# Main.net
KiCad netlist of a schematic drawn in Altium Designer
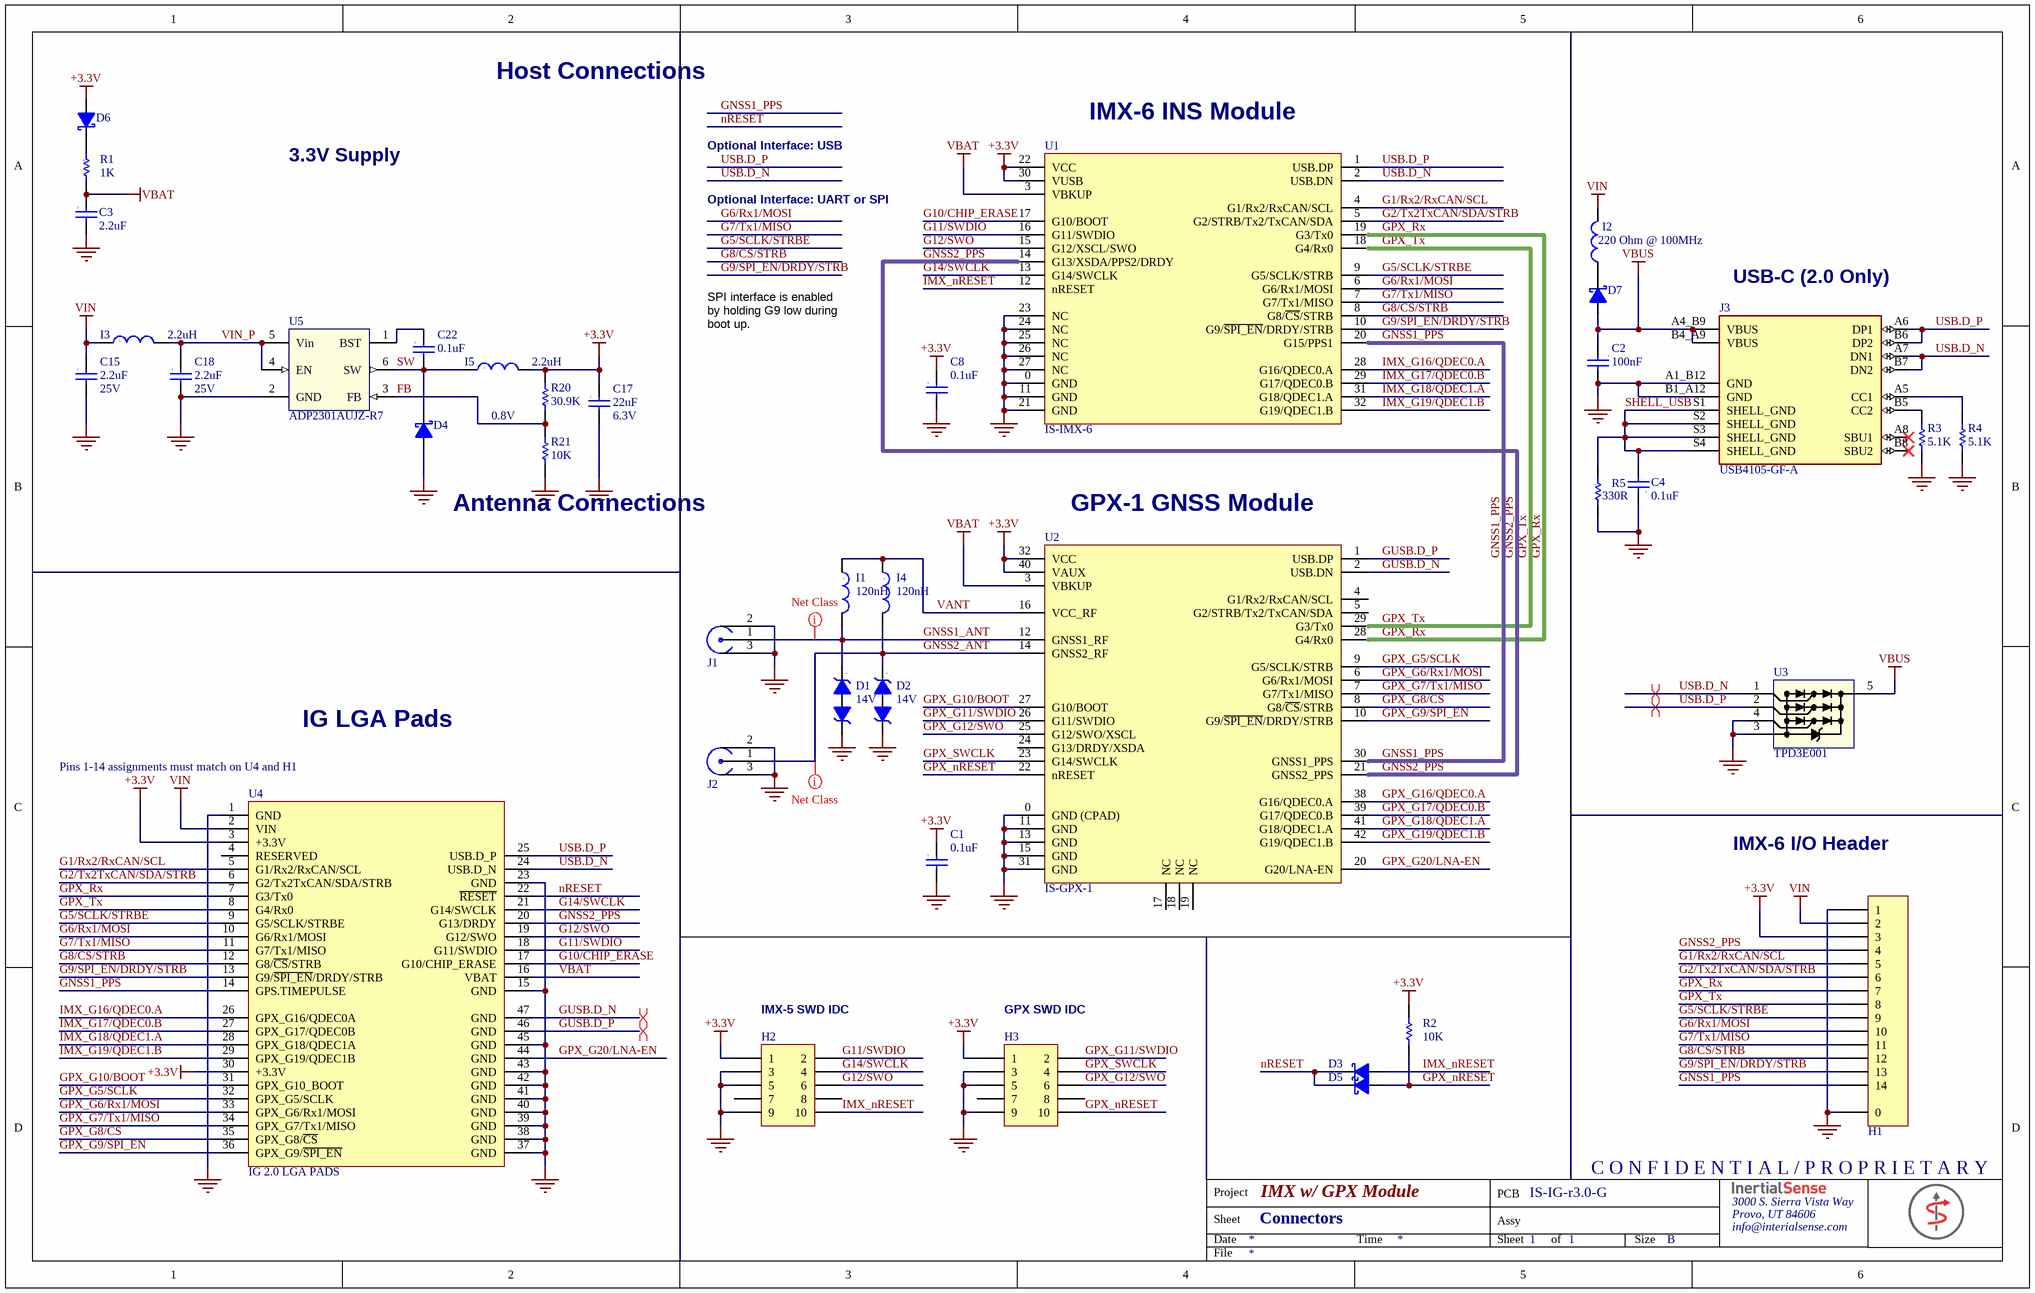
[diagram p0: Main.SchDoc]

(export (version "E")
  (design (tool "Eeschema 10.0.6"))
  (components
    (comp (ref "C1")
      (value "0.1uF")
      (footprint "0402")
      (description "CAP CER .10UF 50V X7R 10% 0402")
      (fields
        (field (name "MANUFACTURER") "TDK Corporation")
        (field (name "MANUFACTURER PART NUMBER") "C1005X7R1H104K")
        (field (name "PUBLISHER") "Altium Limited")
      )
      (libsource (lib "General") (part "Cap"))
    )
    (comp (ref "C2")
      (value "100nF")
      (footprint "0402")
      (description "CAP CER .10UF 50V X7R 10% 0402")
      (fields
        (field (name "MANUFACTURER") "TDK Corporation")
        (field (name "MANUFACTURER PART NUMBER") "C1005X7R1H104K")
        (field (name "PUBLISHER") "Altium Limited")
      )
      (libsource (lib "General") (part "Cap"))
    )
    (comp (ref "C3")
      (value "2.2uF")
      (footprint "0402")
      (description "0402 2.2 uF 6.3 V ±10% Tolerance X6S Multilayer Ceramic Capacitor")
      (fields
        (field (name "MANUFACTURER") "Murata")
        (field (name "MANUFACTURER PART NUMBER") "GRM155C80J225KE95D")
        (field (name "PUBLISHER") "Altium Limited")
      )
      (libsource (lib "General") (part "Cap"))
    )
    (comp (ref "C4")
      (value "0.1uF")
      (footprint "0402")
      (description "CAP CER .10UF 50V X7R 10% 0402")
      (fields
        (field (name "MANUFACTURER") "TDK Corporation")
        (field (name "MANUFACTURER PART NUMBER") "C1005X7R1H104K")
        (field (name "PUBLISHER") "Altium Limited")
      )
      (libsource (lib "General") (part "Cap"))
    )
    (comp (ref "C8")
      (value "0.1uF")
      (footprint "0402")
      (description "CAP CER .10UF 50V X7R 10% 0402")
      (fields
        (field (name "MANUFACTURER") "TDK Corporation")
        (field (name "MANUFACTURER PART NUMBER") "C1005X7R1H104K")
        (field (name "PUBLISHER") "Altium Limited")
      )
      (libsource (lib "General") (part "Cap"))
    )
    (comp (ref "C15")
      (value "2.2uF")
      (footprint "0603")
      (description "CAP CER 2.2UF 25V X6S 0603")
      (fields
        (field (name "MANUFACTURER") "Murata")
        (field (name "MANUFACTURER PART NUMBER") "GRT188C81E225KE13D")
        (field (name "VOLTAGE RATING") "25V")
        (field (name "PUBLISHER") "Altium Limited")
      )
      (libsource (lib "General") (part "Cap"))
    )
    (comp (ref "C17")
      (value "22uF")
      (footprint "0603")
      (description "CAP CER 22UF 6.3V X6S 0603")
      (fields
        (field (name "MANUFACTURER") "Murata")
        (field (name "MANUFACTURER PART NUMBER") "GRM188C80J226ME15D")
        (field (name "VOLTAGE RATING") "6.3V")
        (field (name "PUBLISHER") "Altium Limited")
      )
      (libsource (lib "General") (part "Cap"))
    )
    (comp (ref "C18")
      (value "2.2uF")
      (footprint "0603")
      (description "CAP CER 2.2UF 25V X6S 0603")
      (fields
        (field (name "MANUFACTURER") "Murata")
        (field (name "MANUFACTURER PART NUMBER") "GRT188C81E225KE13D")
        (field (name "VOLTAGE RATING") "25V")
        (field (name "PUBLISHER") "Altium Limited")
      )
      (libsource (lib "General") (part "Cap"))
    )
    (comp (ref "C22")
      (value "0.1uF")
      (footprint "0402")
      (description "CAP CER 0.1UF 50V X7R 0402")
      (fields
        (field (name "MANUFACTURER") "TDK")
        (field (name "MANUFACTURER PART NUMBER") "CGA2B3X7R1H104K050BB")
        (field (name "PUBLISHER") "Altium Limited")
      )
      (libsource (lib "General") (part "Cap"))
    )
    (comp (ref "D1")
      (value "Diode - Bidirectional Zener")
      (footprint "R0402")
      (description "LITTELFUSE - PESD0402-140 - DIODE, ESD PROTECTION, 0402, FULL REEL")
      (fields
        (field (name "MANUFACTURER") "Littelfuse")
        (field (name "MANUFACTURER PART NUMBER") "PESD0402-140")
        (field (name "WORKING VOLTAGE") "14V")
      )
      (libsource (lib "General") (part "Diode - Bidirectional Zener"))
    )
    (comp (ref "D2")
      (value "Diode - Bidirectional Zener")
      (footprint "R0402")
      (description "LITTELFUSE - PESD0402-140 - DIODE, ESD PROTECTION, 0402, FULL REEL")
      (fields
        (field (name "MANUFACTURER") "Littelfuse")
        (field (name "MANUFACTURER PART NUMBER") "PESD0402-140")
        (field (name "WORKING VOLTAGE") "14V")
      )
      (libsource (lib "General") (part "Diode - Bidirectional Zener"))
    )
    (comp (ref "D3")
      (value "Diode - Schottky")
      (footprint "D0402")
      (description "CDBQR0130L; SMT Schottky Diode; 35V 100mA; 2-Pin SOD-923F (0402)")
      (fields (field (name "MANUFACTURER") "Comchip") (field (name "MANUFACTURER PART NUMBER") "CDBQR0130L"))
      (libsource (lib "General") (part "Diode - Schottky"))
    )
    (comp (ref "D4")
      (value "Diode - Schottky")
      (footprint "D0603B")
      (description "DIODE SCHOTTKY 30V 2A 0603")
      (fields
        (field (name "MANUFACTURER") "Vishay")
        (field (name "MANUFACTURER PART NUMBER") "VSKY20301608-G4-08")
      )
      (libsource (lib "General") (part "Diode - Schottky"))
    )
    (comp (ref "D5")
      (value "Diode - Schottky")
      (footprint "D0402")
      (description "CDBQR0130L; SMT Schottky Diode; 35V 100mA; 2-Pin SOD-923F (0402)")
      (fields (field (name "MANUFACTURER") "Comchip") (field (name "MANUFACTURER PART NUMBER") "CDBQR0130L"))
      (libsource (lib "General") (part "Diode - Schottky"))
    )
    (comp (ref "D6")
      (value "Diode - Schottky")
      (footprint "D0603B")
      (description "DIODE SCHOTTKY 30V 2A 0603")
      (fields
        (field (name "MANUFACTURER") "Vishay")
        (field (name "MANUFACTURER PART NUMBER") "VSKY20301608-G4-08")
      )
      (libsource (lib "General") (part "Diode - Schottky"))
    )
    (comp (ref "D7")
      (value "Diode - Schottky")
      (footprint "D0603B")
      (description "DIODE SCHOTTKY 30V 2A 0603")
      (fields
        (field (name "MANUFACTURER") "Vishay")
        (field (name "MANUFACTURER PART NUMBER") "VSKY20301608-G4-08")
      )
      (libsource (lib "General") (part "Diode - Schottky"))
    )
    (comp (ref "H1")
      (value "Hdr - 14pin - mount")
      (footprint "SM14B-GHS-TB(LF)(SN)")
      (description "Conn Shrouded Header HDR 14 POS 1.25mm Solder ST Top Entry SMD T/R")
      (fields
        (field (name "MANUFACTURER") "JST")
        (field (name "MANUFACTURER PART NUMBER") "SM14B-GHS-TB(LF)(SN)")
      )
      (libsource (lib "Connectors") (part "Hdr - 14pin - mount"))
    )
    (comp (ref "H2")
      (value "Hdr - 5x2pin")
      (footprint "FTSH-105-01-L-DV-K-A-P")
      (description "CONN HEADER 10POS DUAL .05\" SMD")
      (fields
        (field (name "MANUFACTURER") "Samtec")
        (field (name "MANUFACTURER PART NUMBER") "FTSH-105-01-L-DV-K-A-P")
      )
      (libsource (lib "Connectors") (part "Hdr - 5x2pin"))
    )
    (comp (ref "H3")
      (value "Hdr - 5x2pin")
      (footprint "FTSH-105-01-L-DV-K-A-P")
      (description "CONN HEADER 10POS DUAL .05\" SMD")
      (fields
        (field (name "MANUFACTURER") "Samtec")
        (field (name "MANUFACTURER PART NUMBER") "FTSH-105-01-L-DV-K-A-P")
      )
      (libsource (lib "Connectors") (part "Hdr - 5x2pin"))
    )
    (comp (ref "I1")
      (value "120nH")
      (footprint "0402")
      (description "Inductor RF Chip Wirewound 120nH 5% 100MHz 20Q-Factor 110mA 2.66Ohm DCR 0402 Paper T/R")
      (fields
        (field (name "MANUFACTURER") "Murata")
        (field (name "MANUFACTURER PART NUMBER") "LQW15ANR12J00D")
      )
      (libsource (lib "") (part "Inductor_1"))
    )
    (comp (ref "I2")
      (value "220 Ohm @ 100MHz")
      (footprint "I0603")
      (description "FERRITE CHIP 220 OHM 2500MA 0603")
      (fields
        (field (name "MANUFACTURER") "Murata Electronics North America")
        (field (name "MANUFACTURER PART NUMBER") "BLM18SG221TN1D")
      )
      (libsource (lib "General") (part "Inductor"))
    )
    (comp (ref "I3")
      (value "2.2uH")
      (footprint "0806")
      (description "FIXED IND 2.2UH 1.2A 110 MOHM")
      (fields
        (field (name "MANUFACTURER") "TDK")
        (field (name "MANUFACTURER PART NUMBER") "MLP2016H2R2MT0S1")
      )
      (libsource (lib "") (part "Inductor_1"))
    )
    (comp (ref "I4")
      (value "120nH")
      (footprint "0402")
      (description "Inductor RF Chip Wirewound 120nH 5% 100MHz 20Q-Factor 110mA 2.66Ohm DCR 0402 Paper T/R")
      (fields
        (field (name "MANUFACTURER") "Murata")
        (field (name "MANUFACTURER PART NUMBER") "LQW15ANR12J00D")
      )
      (libsource (lib "") (part "Inductor_1"))
    )
    (comp (ref "I5")
      (value "2.2uH")
      (footprint "0806")
      (description "FIXED IND 2.2UH 1.2A 110 MOHM")
      (fields
        (field (name "MANUFACTURER") "TDK")
        (field (name "MANUFACTURER PART NUMBER") "MLP2016H2R2MT0S1")
      )
      (libsource (lib "") (part "Inductor_1"))
    )
    (comp (ref "J1")
      (value "RF - GND x 2")
      (footprint "RF UMC SMD")
      (description "CONN UMC RCPT STR 50 OHM SMD")
      (fields
        (field (name "MANUFACTURER") "Emerson Network Power Connectivity Johnson")
        (field (name "MANUFACTURER PART NUMBER") "128-0711-201")
      )
      (libsource (lib "Connectors") (part "RF - GND x 2"))
    )
    (comp (ref "J2")
      (value "RF - GND x 2")
      (footprint "RF UMC SMD")
      (description "CONN UMC RCPT STR 50 OHM SMD")
      (fields
        (field (name "MANUFACTURER") "Emerson Network Power Connectivity Johnson")
        (field (name "MANUFACTURER PART NUMBER") "128-0711-201")
      )
      (libsource (lib "Connectors") (part "RF - GND x 2"))
    )
    (comp (ref "J3")
      (value "USB4105-GF-A")
      (footprint "GCT_USB4105-GF-A")
      (fields (field (name "MANUFACTURER") "GCT"))
      (libsource (lib "Connectors") (part "USB4105-GF-A"))
    )
    (comp (ref "R1")
      (value "1K")
      (footprint "R0402")
      (description "1 kOhms ±1% 0.063W, 1/16W Chip Resistor 0402 (1005 Metric) Moisture Resistant Thick Film")
      (fields
        (field (name "MANUFACTURER") "Yageo")
        (field (name "MANUFACTURER PART NUMBER") "RC0402FR-071KL")
      )
      (libsource (lib "General") (part "Res"))
    )
    (comp (ref "R2")
      (value "10K")
      (footprint "R0402")
      (description "10 kOhms 1% 0.063W, 1/16W Chip Resistor 0402 (1005 Metric) Moisture Resistant Thick Film")
      (fields
        (field (name "MANUFACTURER") "Stackpole Electronics")
        (field (name "MANUFACTURER PART NUMBER") "RMCF0402FT10K0")
      )
      (libsource (lib "General") (part "Res"))
    )
    (comp (ref "R3")
      (value "5.1K")
      (footprint "R0402")
      (description "Res Thick Film 1.0 x 0.5 mm 5.1K Ohm 1% 0.063W(1/16W) 100ppm/ C Molded SMD Paper T/R")
      (fields
        (field (name "MANUFACTURER") "Yageo")
        (field (name "MANUFACTURER PART NUMBER") "RC0402FR-075K1L")
      )
      (libsource (lib "General") (part "Res"))
    )
    (comp (ref "R4")
      (value "5.1K")
      (footprint "R0402")
      (description "Res Thick Film 1.0 x 0.5 mm 5.1K Ohm 1% 0.063W(1/16W) 100ppm/ C Molded SMD Paper T/R")
      (fields
        (field (name "MANUFACTURER") "Yageo")
        (field (name "MANUFACTURER PART NUMBER") "RC0402FR-075K1L")
      )
      (libsource (lib "General") (part "Res"))
    )
    (comp (ref "R5")
      (value "330R")
      (footprint "R0402")
      (description "Res Thick Film 0402 0.33 Ohm 1% 0.125W(1/8W) ±100ppm/C Sulfur Resistant Pad SMD Automotive T/R")
      (fields
        (field (name "MANUFACTURER") "Vishay Dale")
        (field (name "MANUFACTURER PART NUMBER") "RCWE0402R330FKEA")
      )
      (libsource (lib "General") (part "Res"))
    )
    (comp (ref "R20")
      (value "30.9K")
      (footprint "R0402")
      (description "RES TF 30.9K OHM 1% 1/16W 0402")
      (fields
        (field (name "MANUFACTURER") "Stackpole Electronics Inc")
        (field (name "MANUFACTURER PART NUMBER") "RMCF0402FT30K9")
      )
      (libsource (lib "General") (part "Res"))
    )
    (comp (ref "R21")
      (value "10K")
      (footprint "R0402")
      (description "RES 10.0K OHM 1/16W 1% 0402 SMD")
      (fields
        (field (name "MANUFACTURER") "Yageo")
        (field (name "MANUFACTURER PART NUMBER") "RC0402FR-0710KL")
      )
      (libsource (lib "General") (part "Res"))
    )
    (comp (ref "U1")
      (value "IMX")
      (footprint "IS-IMX-6")
      (description "Inertial Sense IMX")
      (fields
        (field (name "MANUFACTURER") "Inertial Sense")
        (field (name "MANUFACTURER PART NUMBER") "IS-IMX-6")
      )
      (libsource (lib "IS-IMX-6") (part "IS-IMX-6"))
    )
    (comp (ref "U2")
      (value "GPX")
      (footprint "IS-GPX-1.0")
      (description "Inertial Sense GPX")
      (fields
        (field (name "MANUFACTURER") "Inertial Sense")
        (field (name "MANUFACTURER PART NUMBER") "IS-GPX-1")
      )
      (libsource (lib "IS-GPX-1") (part "IS-GPX-1.0"))
    )
    (comp (ref "U3")
      (value "TPD3E001")
      (footprint "SOTFL50P160X60-5N")
      (description "TVS DIODE 5.5V SOT5")
      (fields
        (field (name "MANUFACTURER") "Texas Instruments")
        (field (name "MANUFACTURER PART NUMBER") "TPD3E001DRLR")
      )
      (libsource (lib "ICs") (part "TPD3E001"))
    )
    (comp (ref "U4")
      (value "IG 2.0 LGA PADS")
      (footprint "IG-2.0_LGA")
      (description "IMX multi-frequency RTK-GNSS Module")
      (libsource (lib "Sensors") (part "IG_2.0_LGA"))
    )
    (comp (ref "U5")
      (value "ADP2301")
      (footprint "MO-178-AB")
      (description "IC BUCK ADJ 1.2A 6TSOT")
      (fields
        (field (name "MANUFACTURER") "Analog Devices Inc")
        (field (name "MANUFACTURER PART NUMBER") "ADP2301AUJZ-R7")
      )
      (libsource (lib "ICs") (part "ADP2301"))
    )
  )
  (nets
    (net (code "1") (name "+3.3V") (class "Default")
      (node (ref "C1") (pin "1") (pinfunction "1_1") (pintype "passive"))
      (node (ref "C17") (pin "1") (pinfunction "1_1") (pintype "passive"))
      (node (ref "C8") (pin "1") (pinfunction "1_1") (pintype "passive"))
      (node (ref "D6") (pin "A") (pinfunction "A_A") (pintype "passive"))
      (node (ref "H1") (pin "3") (pinfunction "3_3") (pintype "passive"))
      (node (ref "H2") (pin "1") (pinfunction "1_1") (pintype "passive"))
      (node (ref "H3") (pin "1") (pinfunction "1_1") (pintype "passive"))
      (node (ref "I5") (pin "2") (pinfunction "2_2") (pintype "passive"))
      (node (ref "R2") (pin "1") (pinfunction "1_1") (pintype "passive"))
      (node (ref "R20") (pin "2") (pinfunction "2_2") (pintype "passive"))
      (node (ref "U1") (pin "22") (pinfunction "VCC_22") (pintype "power_in"))
      (node (ref "U1") (pin "30") (pinfunction "VUSB_30") (pintype "power_in"))
      (node (ref "U2") (pin "32") (pinfunction "VCC_32") (pintype "power_in"))
      (node (ref "U2") (pin "40") (pinfunction "VAUX_40") (pintype "power_in"))
      (node (ref "U4") (pin "3") (pinfunction "+3.3V_3") (pintype "passive"))
      (node (ref "U4") (pin "30") (pinfunction "+3.3V_30") (pintype "passive"))
    )
    (net (code "2") (name "/FB") (class "Default")
      (node (ref "R20") (pin "1") (pinfunction "1_1") (pintype "passive"))
      (node (ref "R21") (pin "2") (pinfunction "2_2") (pintype "passive"))
      (node (ref "U5") (pin "3") (pinfunction "FB_3") (pintype "input"))
    )
    (net (code "3") (name "/G1{slash}Rx2{slash}RxCAN{slash}SCL") (class "Default")
      (node (ref "H1") (pin "5") (pinfunction "5_5") (pintype "passive"))
      (node (ref "U1") (pin "4") (pinfunction "G1/Rx2/RxCAN/SCL_4") (pintype "passive"))
      (node (ref "U4") (pin "5") (pinfunction "G1/Rx2/RxCAN/SCL_5") (pintype "passive"))
    )
    (net (code "4") (name "/G2{slash}Tx2TxCAN{slash}SDA{slash}STRB") (class "Default")
      (node (ref "H1") (pin "6") (pinfunction "6_6") (pintype "passive"))
      (node (ref "U1") (pin "5") (pinfunction "G2/STRB/Tx2/TxCAN/SDA_5") (pintype "passive"))
      (node (ref "U4") (pin "6") (pinfunction "G2/Tx2TxCAN/SDA/STRB_6") (pintype "passive"))
    )
    (net (code "5") (name "/G5{slash}SCLK{slash}STRBE") (class "Default")
      (node (ref "H1") (pin "9") (pinfunction "9_9") (pintype "passive"))
      (node (ref "U1") (pin "9") (pinfunction "G5/SCLK/STRB_9") (pintype "passive"))
      (node (ref "U4") (pin "9") (pinfunction "G5/SCLK/STRBE_9") (pintype "passive"))
    )
    (net (code "6") (name "/G6{slash}Rx1{slash}MOSI") (class "Default")
      (node (ref "H1") (pin "10") (pinfunction "10_10") (pintype "passive"))
      (node (ref "U1") (pin "6") (pinfunction "G6/Rx1/MOSI_6") (pintype "passive"))
      (node (ref "U4") (pin "10") (pinfunction "G6/Rx1/MOSI_10") (pintype "passive"))
    )
    (net (code "7") (name "/G7{slash}Tx1{slash}MISO") (class "Default")
      (node (ref "H1") (pin "11") (pinfunction "11_11") (pintype "passive"))
      (node (ref "U1") (pin "7") (pinfunction "G7/Tx1/MISO_7") (pintype "passive"))
      (node (ref "U4") (pin "11") (pinfunction "G7/Tx1/MISO_11") (pintype "passive"))
    )
    (net (code "8") (name "/G8{slash}~{CS}{slash}STRB") (class "Default")
      (node (ref "H1") (pin "12") (pinfunction "12_12") (pintype "passive"))
      (node (ref "U1") (pin "8") (pinfunction "G8/~{CS}/STRB_8") (pintype "passive"))
      (node (ref "U4") (pin "12") (pinfunction "G8/~{CS}/STRB_12") (pintype "passive"))
    )
    (net (code "9") (name "/G9{slash}~{SPI_EN}{slash}DRDY{slash}STRB") (class "Default")
      (node (ref "H1") (pin "13") (pinfunction "13_13") (pintype "passive"))
      (node (ref "U1") (pin "10") (pinfunction "G9/~{SPI_EN}/DRDY/STRB_10") (pintype "passive"))
      (node (ref "U4") (pin "13") (pinfunction "G9/~{SPI_EN}/DRDY/STRB_13") (pintype "passive"))
    )
    (net (code "10") (name "/G10{slash}CHIP_ERASE") (class "Default")
      (node (ref "U1") (pin "17") (pinfunction "G10/BOOT_17") (pintype "passive"))
      (node (ref "U4") (pin "17") (pinfunction "G10/CHIP_ERASE_17") (pintype "passive"))
    )
    (net (code "11") (name "/G11{slash}SWDIO") (class "Default")
      (node (ref "H2") (pin "2") (pinfunction "2_2") (pintype "passive"))
      (node (ref "U1") (pin "16") (pinfunction "G11/SWDIO_16") (pintype "passive"))
      (node (ref "U4") (pin "18") (pinfunction "G11/SWDIO_18") (pintype "passive"))
    )
    (net (code "12") (name "/G12{slash}SWO") (class "Default")
      (node (ref "H2") (pin "6") (pinfunction "6_6") (pintype "passive"))
      (node (ref "U1") (pin "15") (pinfunction "G12/XSCL/SWO_15") (pintype "passive"))
      (node (ref "U4") (pin "19") (pinfunction "G12/SWO_19") (pintype "passive"))
    )
    (net (code "13") (name "/G14{slash}SWCLK") (class "Default")
      (node (ref "H2") (pin "4") (pinfunction "4_4") (pintype "passive"))
      (node (ref "U1") (pin "13") (pinfunction "G14/SWCLK_13") (pintype "passive"))
      (node (ref "U4") (pin "21") (pinfunction "G14/SWCLK_21") (pintype "passive"))
    )
    (net (code "14") (name "/GNSS1_ANT") (class "Default")
      (node (ref "D1") (pin "1") (pinfunction "1_1") (pintype "passive"))
      (node (ref "I1") (pin "2") (pinfunction "2_2") (pintype "passive"))
      (node (ref "J1") (pin "1") (pinfunction "1_1") (pintype "passive"))
      (node (ref "U2") (pin "12") (pinfunction "GNSS1_RF_12") (pintype "passive"))
    )
    (net (code "15") (name "/GNSS1_PPS") (class "Default")
      (node (ref "H1") (pin "14") (pinfunction "14_14") (pintype "passive"))
      (node (ref "U1") (pin "20") (pinfunction "G15/PPS1_20") (pintype "passive"))
      (node (ref "U2") (pin "30") (pinfunction "GNSS1_PPS_30") (pintype "passive"))
      (node (ref "U4") (pin "14") (pinfunction "GPS.TIMEPULSE_14") (pintype "passive"))
    )
    (net (code "16") (name "/GNSS2_ANT") (class "Default")
      (node (ref "D2") (pin "1") (pinfunction "1_1") (pintype "passive"))
      (node (ref "I4") (pin "2") (pinfunction "2_2") (pintype "passive"))
      (node (ref "J2") (pin "1") (pinfunction "1_1") (pintype "passive"))
      (node (ref "U2") (pin "14") (pinfunction "GNSS2_RF_14") (pintype "passive"))
    )
    (net (code "17") (name "/GNSS2_PPS") (class "Default")
      (node (ref "H1") (pin "4") (pinfunction "4_4") (pintype "passive"))
      (node (ref "U1") (pin "14") (pinfunction "G13/XSDA/PPS2/DRDY_14") (pintype "passive"))
      (node (ref "U2") (pin "21") (pinfunction "GNSS2_PPS_21") (pintype "passive"))
      (node (ref "U4") (pin "20") (pinfunction "G13/DRDY_20") (pintype "passive"))
    )
    (net (code "18") (name "/GPX_G5{slash}SCLK") (class "Default")
      (node (ref "U2") (pin "9") (pinfunction "G5/SCLK/STRB_9") (pintype "passive"))
      (node (ref "U4") (pin "32") (pinfunction "GPX_G5/SCLK_32") (pintype "passive"))
    )
    (net (code "19") (name "/GPX_G6{slash}Rx1{slash}MOSI") (class "Default")
      (node (ref "U2") (pin "6") (pinfunction "G6/Rx1/MOSI_6") (pintype "passive"))
      (node (ref "U4") (pin "33") (pinfunction "GPX_G6/Rx1/MOSI_33") (pintype "passive"))
    )
    (net (code "20") (name "/GPX_G7{slash}Tx1{slash}MISO") (class "Default")
      (node (ref "U2") (pin "7") (pinfunction "G7/Tx1/MISO_7") (pintype "passive"))
      (node (ref "U4") (pin "34") (pinfunction "GPX_G7/Tx1/MISO_34") (pintype "passive"))
    )
    (net (code "21") (name "/GPX_G8{slash}~{CS}") (class "Default")
      (node (ref "U2") (pin "8") (pinfunction "G8/~{CS}/STRB_8") (pintype "passive"))
      (node (ref "U4") (pin "35") (pinfunction "GPX_G8/~{CS}_35") (pintype "passive"))
    )
    (net (code "22") (name "/GPX_G9{slash}~{SPI_EN}") (class "Default")
      (node (ref "U2") (pin "10") (pinfunction "G9/~{SPI_EN}/DRDY/STRB_10") (pintype "passive"))
      (node (ref "U4") (pin "36") (pinfunction "GPX_G9/~{SPI_EN}_36") (pintype "passive"))
    )
    (net (code "23") (name "/GPX_G10{slash}BOOT") (class "Default")
      (node (ref "U2") (pin "27") (pinfunction "G10/BOOT_27") (pintype "passive"))
      (node (ref "U4") (pin "31") (pinfunction "GPX_G10_BOOT_31") (pintype "passive"))
    )
    (net (code "24") (name "/GPX_G11{slash}SWDIO") (class "Default")
      (node (ref "H3") (pin "2") (pinfunction "2_2") (pintype "passive"))
      (node (ref "U2") (pin "26") (pinfunction "G11/SWDIO_26") (pintype "passive"))
    )
    (net (code "25") (name "/GPX_G12{slash}SWO") (class "Default")
      (node (ref "H3") (pin "6") (pinfunction "6_6") (pintype "passive"))
      (node (ref "U2") (pin "25") (pinfunction "G12/SWO/XSCL_25") (pintype "passive"))
    )
    (net (code "26") (name "/GPX_G16{slash}QDEC0.A") (class "Default")
      (node (ref "U2") (pin "38") (pinfunction "G16/QDEC0.A_38") (pintype "passive"))
    )
    (net (code "27") (name "/GPX_G17{slash}QDEC0.B") (class "Default")
      (node (ref "U2") (pin "39") (pinfunction "G17/QDEC0.B_39") (pintype "passive"))
    )
    (net (code "28") (name "/GPX_G18{slash}QDEC1.A") (class "Default")
      (node (ref "U2") (pin "41") (pinfunction "G18/QDEC1.A_41") (pintype "passive"))
    )
    (net (code "29") (name "/GPX_G19{slash}QDEC1.B") (class "Default")
      (node (ref "U2") (pin "42") (pinfunction "G19/QDEC1.B_42") (pintype "passive"))
    )
    (net (code "30") (name "/GPX_G20{slash}LNA-EN") (class "Default")
      (node (ref "U2") (pin "20") (pinfunction "G20/LNA-EN_20") (pintype "passive"))
      (node (ref "U4") (pin "44") (pinfunction "GND_44") (pintype "passive"))
    )
    (net (code "31") (name "/GPX_Rx") (class "Default")
      (node (ref "H1") (pin "7") (pinfunction "7_7") (pintype "passive"))
      (node (ref "U1") (pin "19") (pinfunction "G3/Tx0_19") (pintype "passive"))
      (node (ref "U2") (pin "28") (pinfunction "G4/Rx0_28") (pintype "passive"))
      (node (ref "U4") (pin "7") (pinfunction "G3/Tx0_7") (pintype "passive"))
    )
    (net (code "32") (name "/GPX_SWCLK") (class "Default")
      (node (ref "H3") (pin "4") (pinfunction "4_4") (pintype "passive"))
      (node (ref "U2") (pin "23") (pinfunction "G14/SWCLK_23") (pintype "passive"))
    )
    (net (code "33") (name "/GPX_Tx") (class "Default")
      (node (ref "H1") (pin "8") (pinfunction "8_8") (pintype "passive"))
      (node (ref "U1") (pin "18") (pinfunction "G4/Rx0_18") (pintype "passive"))
      (node (ref "U2") (pin "29") (pinfunction "G3/Tx0_29") (pintype "passive"))
      (node (ref "U4") (pin "8") (pinfunction "G4/Rx0_8") (pintype "passive"))
    )
    (net (code "34") (name "/GPX_nRESET") (class "Default")
      (node (ref "D5") (pin "A") (pinfunction "A_A") (pintype "passive"))
      (node (ref "H3") (pin "10") (pinfunction "10_10") (pintype "passive"))
      (node (ref "R2") (pin "2") (pinfunction "2_2") (pintype "passive"))
      (node (ref "U2") (pin "22") (pinfunction "nRESET_22") (pintype "passive"))
    )
    (net (code "35") (name "/GUSB.D_N") (class "Default")
      (node (ref "U2") (pin "2") (pinfunction "USB.DN_2") (pintype "passive"))
      (node (ref "U4") (pin "47") (pinfunction "GND_47") (pintype "passive"))
    )
    (net (code "36") (name "/GUSB.D_P") (class "Default")
      (node (ref "U2") (pin "1") (pinfunction "USB.DP_1") (pintype "passive"))
      (node (ref "U4") (pin "46") (pinfunction "GND_46") (pintype "passive"))
    )
    (net (code "37") (name "/IMX_G16{slash}QDEC0.A") (class "Default")
      (node (ref "U1") (pin "28") (pinfunction "G16/QDEC0.A_28") (pintype "passive"))
      (node (ref "U4") (pin "26") (pinfunction "GPX_G16/QDEC0A_26") (pintype "passive"))
    )
    (net (code "38") (name "/IMX_G17{slash}QDEC0.B") (class "Default")
      (node (ref "U1") (pin "29") (pinfunction "G17/QDEC0.B_29") (pintype "passive"))
      (node (ref "U4") (pin "27") (pinfunction "GPX_G17/QDEC0B_27") (pintype "passive"))
    )
    (net (code "39") (name "/IMX_G18{slash}QDEC1.A") (class "Default")
      (node (ref "U1") (pin "31") (pinfunction "G18/QDEC1.A_31") (pintype "passive"))
      (node (ref "U4") (pin "28") (pinfunction "GPX_G18/QDEC1A_28") (pintype "passive"))
    )
    (net (code "40") (name "/IMX_G19{slash}QDEC1.B") (class "Default")
      (node (ref "U1") (pin "32") (pinfunction "G19/QDEC1.B_32") (pintype "passive"))
      (node (ref "U4") (pin "29") (pinfunction "GPX_G19/QDEC1B_29") (pintype "passive"))
    )
    (net (code "41") (name "/IMX_nRESET") (class "Default")
      (node (ref "D3") (pin "A") (pinfunction "A_A") (pintype "passive"))
      (node (ref "H2") (pin "10") (pinfunction "10_10") (pintype "passive"))
      (node (ref "U1") (pin "12") (pinfunction "nRESET_12") (pintype "passive"))
    )
    (net (code "42") (name "/SHELL_USB") (class "Default")
      (node (ref "C4") (pin "2") (pinfunction "2_2") (pintype "passive"))
      (node (ref "J3") (pin "S1") (pinfunction "SHELL_GND_S1") (pintype "power_in"))
      (node (ref "J3") (pin "S2") (pinfunction "SHELL_GND_S2") (pintype "power_in"))
      (node (ref "J3") (pin "S3") (pinfunction "SHELL_GND_S3") (pintype "power_in"))
      (node (ref "J3") (pin "S4") (pinfunction "SHELL_GND_S4") (pintype "power_in"))
      (node (ref "R5") (pin "1") (pinfunction "1_1") (pintype "passive"))
    )
    (net (code "43") (name "/SW") (class "Default")
      (node (ref "C22") (pin "2") (pinfunction "2_2") (pintype "passive"))
      (node (ref "D4") (pin "C") (pinfunction "C_C") (pintype "passive"))
      (node (ref "I5") (pin "1") (pinfunction "1_1") (pintype "passive"))
      (node (ref "U5") (pin "6") (pinfunction "SW_6") (pintype "output"))
    )
    (net (code "44") (name "/USB.D_N") (class "Default")
      (node (ref "J3") (pin "A7") (pinfunction "DN1_A7") (pintype "bidirectional"))
      (node (ref "J3") (pin "B7") (pinfunction "DN2_B7") (pintype "bidirectional"))
      (node (ref "U1") (pin "2") (pinfunction "USB.DN_2") (pintype "passive"))
      (node (ref "U3") (pin "1") (pintype "passive"))
      (node (ref "U4") (pin "24") (pinfunction "USB.D_N_24") (pintype "passive"))
    )
    (net (code "45") (name "/USB.D_P") (class "Default")
      (node (ref "J3") (pin "A6") (pinfunction "DP1_A6") (pintype "bidirectional"))
      (node (ref "J3") (pin "B6") (pinfunction "DP2_B6") (pintype "bidirectional"))
      (node (ref "U1") (pin "1") (pinfunction "USB.DP_1") (pintype "passive"))
      (node (ref "U3") (pin "2") (pintype "passive"))
      (node (ref "U4") (pin "25") (pinfunction "USB.D_P_25") (pintype "passive"))
    )
    (net (code "46") (name "/VANT") (class "Default")
      (node (ref "I1") (pin "1") (pinfunction "1_1") (pintype "passive"))
      (node (ref "I4") (pin "1") (pinfunction "1_1") (pintype "passive"))
      (node (ref "U2") (pin "16") (pinfunction "VCC_RF_16") (pintype "power_in"))
    )
    (net (code "47") (name "/VIN_P") (class "Default")
      (node (ref "C18") (pin "1") (pinfunction "1_1") (pintype "passive"))
      (node (ref "I3") (pin "2") (pinfunction "2_2") (pintype "passive"))
      (node (ref "U5") (pin "4") (pinfunction "EN_4") (pintype "input"))
      (node (ref "U5") (pin "5") (pinfunction "Vin_5") (pintype "power_in"))
    )
    (net (code "48") (name "/nRESET") (class "Default")
      (node (ref "D3") (pin "C") (pinfunction "C_C") (pintype "passive"))
      (node (ref "D5") (pin "C") (pinfunction "C_C") (pintype "passive"))
      (node (ref "U4") (pin "22") (pinfunction "~{RESET}_22") (pintype "passive"))
    )
    (net (code "49") (name "GND") (class "Default")
      (node (ref "C1") (pin "2") (pinfunction "2_2") (pintype "passive"))
      (node (ref "C15") (pin "2") (pinfunction "2_2") (pintype "passive"))
      (node (ref "C17") (pin "2") (pinfunction "2_2") (pintype "passive"))
      (node (ref "C18") (pin "2") (pinfunction "2_2") (pintype "passive"))
      (node (ref "C2") (pin "2") (pinfunction "2_2") (pintype "passive"))
      (node (ref "C3") (pin "2") (pinfunction "2_2") (pintype "passive"))
      (node (ref "C4") (pin "1") (pinfunction "1_1") (pintype "passive"))
      (node (ref "C8") (pin "2") (pinfunction "2_2") (pintype "passive"))
      (node (ref "D1") (pin "2") (pinfunction "2_2") (pintype "passive"))
      (node (ref "D2") (pin "2") (pinfunction "2_2") (pintype "passive"))
      (node (ref "D4") (pin "A") (pinfunction "A_A") (pintype "passive"))
      (node (ref "H1") (pin "0") (pinfunction "0_0") (pintype "passive"))
      (node (ref "H1") (pin "1") (pinfunction "1_1") (pintype "passive"))
      (node (ref "H2") (pin "3") (pinfunction "3_3") (pintype "passive"))
      (node (ref "H2") (pin "5") (pinfunction "5_5") (pintype "passive"))
      (node (ref "H2") (pin "9") (pinfunction "9_9") (pintype "passive"))
      (node (ref "H3") (pin "3") (pinfunction "3_3") (pintype "passive"))
      (node (ref "H3") (pin "5") (pinfunction "5_5") (pintype "passive"))
      (node (ref "H3") (pin "9") (pinfunction "9_9") (pintype "passive"))
      (node (ref "J1") (pin "2") (pinfunction "2_2") (pintype "passive"))
      (node (ref "J1") (pin "3") (pinfunction "3_3") (pintype "passive"))
      (node (ref "J2") (pin "2") (pinfunction "2_2") (pintype "passive"))
      (node (ref "J2") (pin "3") (pinfunction "3_3") (pintype "passive"))
      (node (ref "J3") (pin "A1_B12") (pinfunction "GND_A1_B12") (pintype "power_in"))
      (node (ref "J3") (pin "B1_A12") (pinfunction "GND_B1_A12") (pintype "power_in"))
      (node (ref "R21") (pin "1") (pinfunction "1_1") (pintype "passive"))
      (node (ref "R3") (pin "1") (pinfunction "1_1") (pintype "passive"))
      (node (ref "R4") (pin "1") (pinfunction "1_1") (pintype "passive"))
      (node (ref "R5") (pin "2") (pinfunction "2_2") (pintype "passive"))
      (node (ref "U1") (pin "0") (pinfunction "GND_0") (pintype "power_in"))
      (node (ref "U1") (pin "11") (pinfunction "GND_11") (pintype "power_in"))
      (node (ref "U1") (pin "21") (pinfunction "GND_21") (pintype "power_in"))
      (node (ref "U1") (pin "23") (pinfunction "NC_23") (pintype "power_in"))
      (node (ref "U1") (pin "24") (pinfunction "NC_24") (pintype "power_in"))
      (node (ref "U1") (pin "25") (pinfunction "NC_25") (pintype "power_in"))
      (node (ref "U1") (pin "26") (pinfunction "NC_26") (pintype "power_in"))
      (node (ref "U1") (pin "27") (pinfunction "NC_27") (pintype "power_in"))
      (node (ref "U2") (pin "0") (pinfunction "GND_(CPAD)_0") (pintype "power_in"))
      (node (ref "U2") (pin "11") (pinfunction "GND_11") (pintype "power_in"))
      (node (ref "U2") (pin "13") (pinfunction "GND_13") (pintype "power_in"))
      (node (ref "U2") (pin "15") (pinfunction "GND_15") (pintype "power_in"))
      (node (ref "U2") (pin "31") (pinfunction "GND_31") (pintype "power_in"))
      (node (ref "U3") (pin "3") (pintype "passive"))
      (node (ref "U3") (pin "4") (pinfunction "nc_4") (pintype "passive"))
      (node (ref "U4") (pin "1") (pinfunction "GND_1") (pintype "passive"))
      (node (ref "U4") (pin "15") (pinfunction "GND_15") (pintype "passive"))
      (node (ref "U4") (pin "23") (pinfunction "GND_23") (pintype "passive"))
      (node (ref "U4") (pin "37") (pinfunction "GND_37") (pintype "passive"))
      (node (ref "U4") (pin "38") (pinfunction "GND_38") (pintype "passive"))
      (node (ref "U4") (pin "39") (pinfunction "GND_39") (pintype "passive"))
      (node (ref "U4") (pin "40") (pinfunction "GND_40") (pintype "passive"))
      (node (ref "U4") (pin "41") (pinfunction "GND_41") (pintype "passive"))
      (node (ref "U4") (pin "42") (pinfunction "GND_42") (pintype "passive"))
      (node (ref "U4") (pin "43") (pinfunction "GND_43") (pintype "passive"))
      (node (ref "U4") (pin "45") (pinfunction "GND_45") (pintype "passive"))
      (node (ref "U5") (pin "2") (pinfunction "GND_2") (pintype "power_in"))
    )
    (net (code "50") (name "Net-(D6-PadC)") (class "Default")
      (node (ref "D6") (pin "C") (pinfunction "C_C") (pintype "passive"))
      (node (ref "R1") (pin "1") (pinfunction "1_1") (pintype "passive"))
    )
    (net (code "51") (name "Net-(D7-PadC)") (class "Default")
      (node (ref "D7") (pin "C") (pinfunction "C_C") (pintype "passive"))
      (node (ref "I2") (pin "2") (pinfunction "2_2") (pintype "passive"))
    )
    (net (code "52") (name "Net-(J3-CC1)") (class "Default")
      (node (ref "J3") (pin "A5") (pinfunction "CC1_A5") (pintype "bidirectional"))
      (node (ref "R4") (pin "2") (pinfunction "2_2") (pintype "passive"))
    )
    (net (code "53") (name "Net-(J3-CC2)") (class "Default")
      (node (ref "J3") (pin "B5") (pinfunction "CC2_B5") (pintype "bidirectional"))
      (node (ref "R3") (pin "2") (pinfunction "2_2") (pintype "passive"))
    )
    (net (code "54") (name "Net-(U5-BST)") (class "Default")
      (node (ref "C22") (pin "1") (pinfunction "1_1") (pintype "passive"))
      (node (ref "U5") (pin "1") (pinfunction "BST_1") (pintype "passive"))
    )
    (net (code "55") (name "VBAT") (class "Default")
      (node (ref "C3") (pin "1") (pinfunction "1_1") (pintype "passive"))
      (node (ref "R1") (pin "2") (pinfunction "2_2") (pintype "passive"))
      (node (ref "U1") (pin "3") (pinfunction "VBKUP_3") (pintype "passive"))
      (node (ref "U2") (pin "3") (pinfunction "VBKUP_3") (pintype "passive"))
      (node (ref "U4") (pin "16") (pinfunction "VBAT_16") (pintype "passive"))
    )
    (net (code "56") (name "VBUS") (class "Default")
      (node (ref "C2") (pin "1") (pinfunction "1_1") (pintype "passive"))
      (node (ref "D7") (pin "A") (pinfunction "A_A") (pintype "passive"))
      (node (ref "J3") (pin "A4_B9") (pinfunction "VBUS_A4_B9") (pintype "passive"))
      (node (ref "J3") (pin "B4_A9") (pinfunction "VBUS_B4_A9") (pintype "passive"))
      (node (ref "U3") (pin "5") (pinfunction "nc_5") (pintype "passive"))
    )
    (net (code "57") (name "VIN") (class "Default")
      (node (ref "C15") (pin "1") (pinfunction "1_1") (pintype "passive"))
      (node (ref "H1") (pin "2") (pinfunction "2_2") (pintype "passive"))
      (node (ref "I2") (pin "1") (pinfunction "1_1") (pintype "passive"))
      (node (ref "I3") (pin "1") (pinfunction "1_1") (pintype "passive"))
      (node (ref "U4") (pin "2") (pinfunction "VIN_2") (pintype "passive"))
    )
    (net (code "58") (name "unconnected-(H2-Pad7)") (class "Default")
      (node (ref "H2") (pin "7") (pinfunction "7_7") (pintype "passive"))
    )
    (net (code "59") (name "unconnected-(H2-Pad8)") (class "Default")
      (node (ref "H2") (pin "8") (pinfunction "8_8") (pintype "passive"))
    )
    (net (code "60") (name "unconnected-(H3-Pad7)") (class "Default")
      (node (ref "H3") (pin "7") (pinfunction "7_7") (pintype "passive"))
    )
    (net (code "61") (name "unconnected-(H3-Pad8)") (class "Default")
      (node (ref "H3") (pin "8") (pinfunction "8_8") (pintype "passive"))
    )
    (net (code "62") (name "unconnected-(J3-SBU1-PadA8)") (class "Default")
      (node (ref "J3") (pin "A8") (pinfunction "SBU1_A8") (pintype "bidirectional+no_connect"))
    )
    (net (code "63") (name "unconnected-(J3-SBU2-PadB8)") (class "Default")
      (node (ref "J3") (pin "B8") (pinfunction "SBU2_B8") (pintype "bidirectional+no_connect"))
    )
    (net (code "64") (name "unconnected-(U2-G1{slash}Rx2{slash}RxCAN{slash}SCL-Pad4)") (class "Default")
      (node (ref "U2") (pin "4") (pinfunction "G1/Rx2/RxCAN/SCL_4") (pintype "passive"))
    )
    (net (code "65") (name "unconnected-(U2-G2{slash}STRB{slash}Tx2{slash}TxCAN{slash}SDA-Pad5)") (class "Default")
      (node (ref "U2") (pin "5") (pinfunction "G2/STRB/Tx2/TxCAN/SDA_5") (pintype "passive"))
    )
    (net (code "66") (name "unconnected-(U2-G13{slash}DRDY{slash}XSDA-Pad24)") (class "Default")
      (node (ref "U2") (pin "24") (pinfunction "G13/DRDY/XSDA_24") (pintype "passive"))
    )
    (net (code "67") (name "unconnected-(U2-NC-Pad17)") (class "Default")
      (node (ref "U2") (pin "17") (pinfunction "NC_17") (pintype "passive"))
    )
    (net (code "68") (name "unconnected-(U2-NC-Pad18)") (class "Default")
      (node (ref "U2") (pin "18") (pinfunction "NC_18") (pintype "passive"))
    )
    (net (code "69") (name "unconnected-(U2-NC-Pad19)") (class "Default")
      (node (ref "U2") (pin "19") (pinfunction "NC_19") (pintype "passive"))
    )
    (net (code "70") (name "unconnected-(U4-RESERVED-Pad4)") (class "Default")
      (node (ref "U4") (pin "4") (pinfunction "RESERVED_4") (pintype "passive"))
    )
  )
)
